# EH4a-midi-v1_4_poprawiona_na_przysz_o.net
KiCad netlist of a schematic drawn in EAGLE
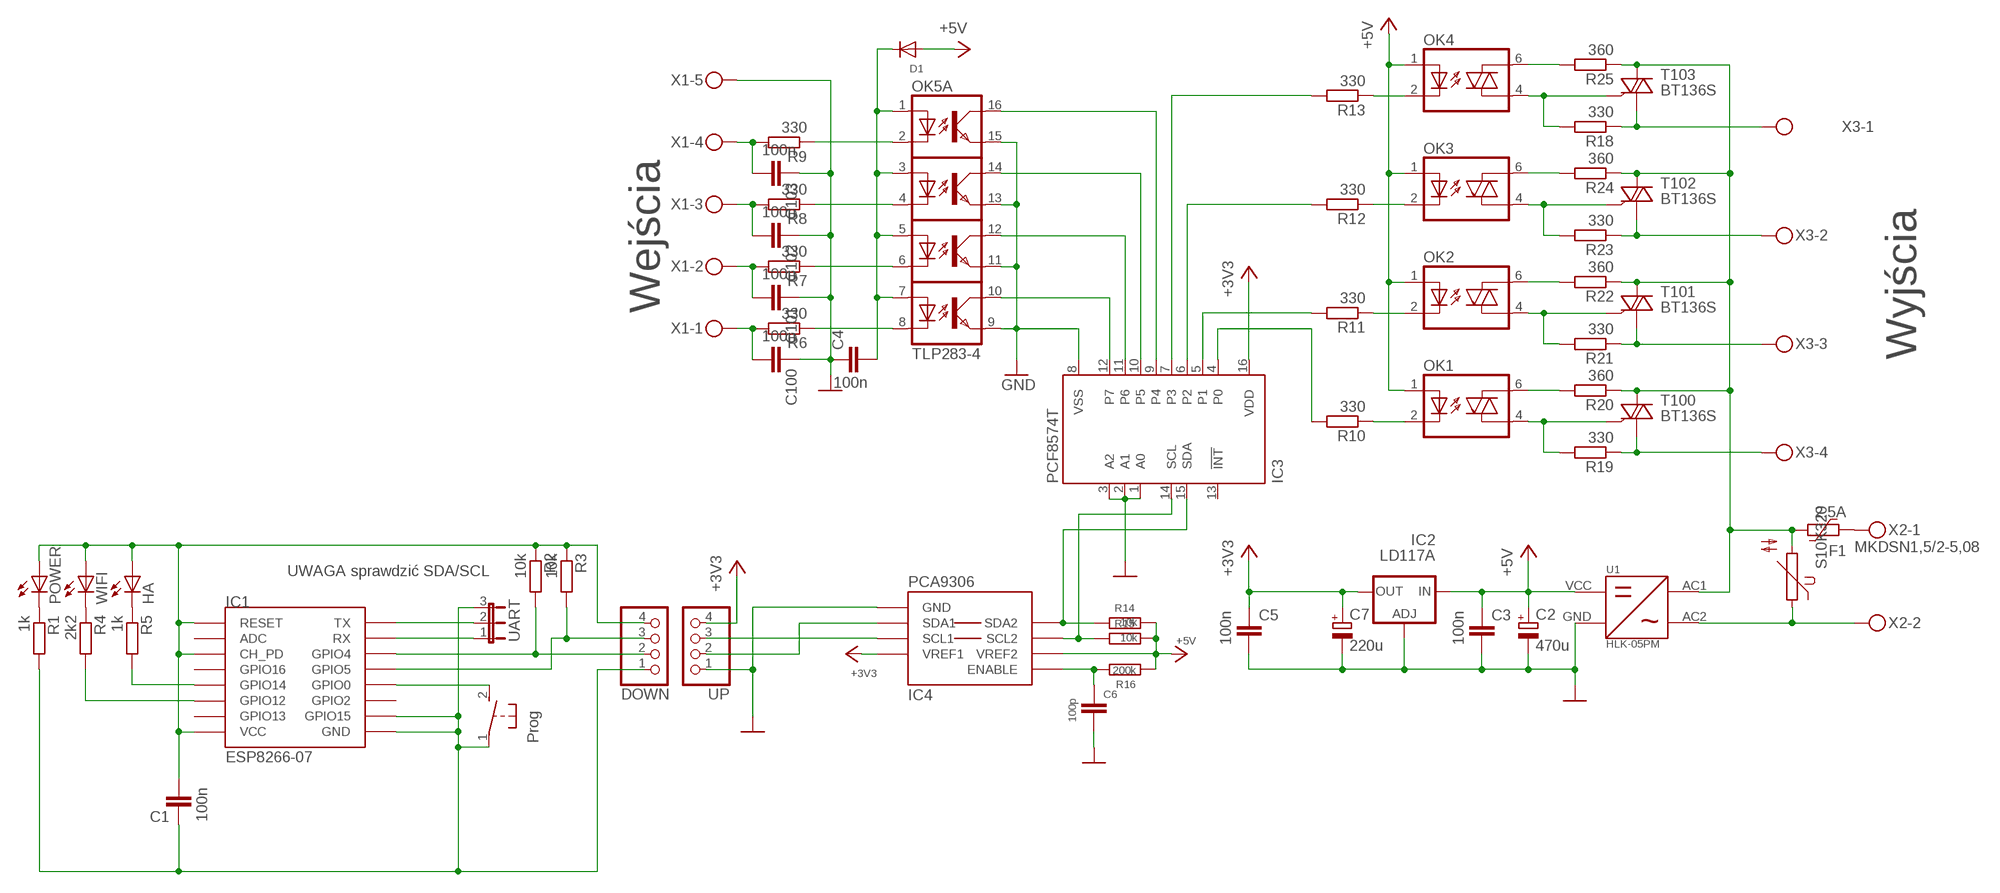
[diagram p0: schematic, sheet 1]

(export (version "E")
  (design (tool "Eeschema 10.0.6"))
  (components
    (comp (ref "C1")
      (value "100n")
      (footprint "eagle-import:C0805")
      (libsource (lib "eagle-import") (part "C-EUC0805"))
    )
    (comp (ref "C2")
      (value "470u")
      (footprint "eagle-import:E3,5-8")
      (libsource (lib "eagle-import") (part "CPOL-EUE3.5-8"))
    )
    (comp (ref "C3")
      (value "100n")
      (footprint "eagle-import:C0805")
      (libsource (lib "eagle-import") (part "C-EUC0805"))
    )
    (comp (ref "C4")
      (value "100n")
      (footprint "eagle-import:C0805")
      (libsource (lib "eagle-import") (part "C-EUC0805"))
    )
    (comp (ref "C5")
      (value "100n")
      (footprint "eagle-import:C0805")
      (libsource (lib "eagle-import") (part "C-EUC0805"))
    )
    (comp (ref "C6")
      (value "100p")
      (footprint "eagle-import:C0805")
      (libsource (lib "eagle-import") (part "C-EUC0805"))
    )
    (comp (ref "C7")
      (value "220u")
      (footprint "eagle-import:E2,5-7")
      (libsource (lib "eagle-import") (part "CPOL-EUE2.5-7"))
    )
    (comp (ref "C100")
      (value "100n")
      (footprint "eagle-import:C0805")
      (libsource (lib "eagle-import") (part "C-EUC0805"))
    )
    (comp (ref "C101")
      (value "100n")
      (footprint "eagle-import:C0805")
      (libsource (lib "eagle-import") (part "C-EUC0805"))
    )
    (comp (ref "C102")
      (value "100n")
      (footprint "eagle-import:C0805")
      (libsource (lib "eagle-import") (part "C-EUC0805"))
    )
    (comp (ref "C103")
      (value "100n")
      (footprint "eagle-import:C0805")
      (libsource (lib "eagle-import") (part "C-EUC0805"))
    )
    (comp (ref "D1")
      (value "1N4148")
      (footprint "eagle-import:SOD-123")
      (libsource (lib "eagle-import") (part "DIODESOD-123"))
    )
    (comp (ref "DOWN")
      (value "PINHD-1X4")
      (footprint "eagle-import:1X04")
      (libsource (lib "eagle-import") (part "PINHD-1X4"))
    )
    (comp (ref "F1")
      (value "2.5A")
      (footprint "eagle-import:2920L")
      (fields (field (name "MF") "Littelfuse") (field (name "MPN") "2920L700SL"))
      (libsource (lib "eagle-import") (part "?2920L700SL"))
    )
    (comp (ref "HA")
      (value "LED3MM")
      (footprint "eagle-import:LED3MM")
      (libsource (lib "eagle-import") (part "LED3MM"))
    )
    (comp (ref "IC1")
      (value "ESP8266-07")
      (footprint "eagle-import:ESP12")
      (libsource (lib "eagle-import") (part "ESP12"))
    )
    (comp (ref "IC2")
      (value "LD117A")
      (footprint "eagle-import:SOT223")
      (libsource (lib "eagle-import") (part "LD117A?S12TR"))
    )
    (comp (ref "IC3")
      (value "PCF8574T")
      (footprint "eagle-import:SO16W")
      (fields (field (name "MPN") "PCF8574T/3,512"))
      (libsource (lib "eagle-import") (part "PCF8574T"))
    )
    (comp (ref "IC4")
      (value "PCA9306")
      (footprint "eagle-import:MSOP08")
      (libsource (lib "eagle-import") (part "IC2_LEVEL_TRANSLATER"))
    )
    (comp (ref "OK1")
      (value "MOC3043")
      (footprint "eagle-import:DIL06")
      (libsource (lib "eagle-import") (part "IL420"))
    )
    (comp (ref "OK2")
      (value "IL420")
      (footprint "eagle-import:DIL06")
      (libsource (lib "eagle-import") (part "IL420"))
    )
    (comp (ref "OK3")
      (value "IL420")
      (footprint "eagle-import:DIL06")
      (libsource (lib "eagle-import") (part "IL420"))
    )
    (comp (ref "OK4")
      (value "IL420")
      (footprint "eagle-import:DIL06")
      (libsource (lib "eagle-import") (part "IL420"))
    )
    (comp (ref "OK5")
      (value "TLP283-4")
      (footprint "eagle-import:MINI-FLAT-16")
      (libsource (lib "eagle-import") (part "TLP283-4"))
    )
    (comp (ref "POWER")
      (value "LED3MM")
      (footprint "eagle-import:LED3MM")
      (libsource (lib "eagle-import") (part "LED3MM"))
    )
    (comp (ref "R1")
      (value "1k")
      (footprint "eagle-import:M0805")
      (libsource (lib "eagle-import") (part "rcl_334_R-EU_M0805"))
    )
    (comp (ref "R2")
      (value "10k")
      (footprint "eagle-import:M0805")
      (libsource (lib "eagle-import") (part "rcl_334_R-EU_M0805"))
    )
    (comp (ref "R3")
      (value "10k")
      (footprint "eagle-import:M0805")
      (libsource (lib "eagle-import") (part "rcl_334_R-EU_M0805"))
    )
    (comp (ref "R4")
      (value "2k2")
      (footprint "eagle-import:M0805")
      (libsource (lib "eagle-import") (part "rcl_334_R-EU_M0805"))
    )
    (comp (ref "R5")
      (value "1k")
      (footprint "eagle-import:M0805")
      (libsource (lib "eagle-import") (part "rcl_334_R-EU_M0805"))
    )
    (comp (ref "R6")
      (value "330")
      (footprint "eagle-import:M0805")
      (libsource (lib "eagle-import") (part "rcl_334_R-EU_M0805"))
    )
    (comp (ref "R7")
      (value "330")
      (footprint "eagle-import:M0805")
      (libsource (lib "eagle-import") (part "rcl_334_R-EU_M0805"))
    )
    (comp (ref "R8")
      (value "330")
      (footprint "eagle-import:M0805")
      (libsource (lib "eagle-import") (part "rcl_334_R-EU_M0805"))
    )
    (comp (ref "R9")
      (value "330")
      (footprint "eagle-import:M0805")
      (libsource (lib "eagle-import") (part "rcl_334_R-EU_M0805"))
    )
    (comp (ref "R10")
      (value "330")
      (footprint "eagle-import:M0805")
      (libsource (lib "eagle-import") (part "rcl_334_R-EU_M0805"))
    )
    (comp (ref "R11")
      (value "330")
      (footprint "eagle-import:M0805")
      (libsource (lib "eagle-import") (part "rcl_334_R-EU_M0805"))
    )
    (comp (ref "R12")
      (value "330")
      (footprint "eagle-import:M0805")
      (libsource (lib "eagle-import") (part "rcl_334_R-EU_M0805"))
    )
    (comp (ref "R13")
      (value "330")
      (footprint "eagle-import:M0805")
      (libsource (lib "eagle-import") (part "rcl_334_R-EU_M0805"))
    )
    (comp (ref "R14")
      (value "10k")
      (footprint "eagle-import:R0805")
      (libsource (lib "eagle-import") (part "R-EU_R0805"))
    )
    (comp (ref "R15")
      (value "10k")
      (footprint "eagle-import:R0805")
      (libsource (lib "eagle-import") (part "R-EU_R0805"))
    )
    (comp (ref "R16")
      (value "200k")
      (footprint "eagle-import:R0805")
      (libsource (lib "eagle-import") (part "R-EU_R0805"))
    )
    (comp (ref "R17")
      (value "S10K320")
      (footprint "eagle-import:S10K320")
      (libsource (lib "eagle-import") (part "S10K320"))
    )
    (comp (ref "R18")
      (value "330")
      (footprint "eagle-import:R1210")
      (libsource (lib "eagle-import") (part "R-EU_R1210"))
    )
    (comp (ref "R19")
      (value "330")
      (footprint "eagle-import:R1210")
      (libsource (lib "eagle-import") (part "R-EU_R1210"))
    )
    (comp (ref "R20")
      (value "360")
      (footprint "eagle-import:R1210")
      (libsource (lib "eagle-import") (part "R-EU_R1210"))
    )
    (comp (ref "R21")
      (value "330")
      (footprint "eagle-import:R1210")
      (libsource (lib "eagle-import") (part "R-EU_R1210"))
    )
    (comp (ref "R22")
      (value "360")
      (footprint "eagle-import:R1210")
      (libsource (lib "eagle-import") (part "R-EU_R1210"))
    )
    (comp (ref "R23")
      (value "330")
      (footprint "eagle-import:R1210")
      (libsource (lib "eagle-import") (part "R-EU_R1210"))
    )
    (comp (ref "R24")
      (value "360")
      (footprint "eagle-import:R1210")
      (libsource (lib "eagle-import") (part "R-EU_R1210"))
    )
    (comp (ref "R25")
      (value "360")
      (footprint "eagle-import:R1210")
      (libsource (lib "eagle-import") (part "R-EU_R1210"))
    )
    (comp (ref "S1")
      (value "Prog")
      (footprint "eagle-import:DTSM-3")
      (libsource (lib "eagle-import") (part "DTSM-3"))
    )
    (comp (ref "T100")
      (value "BT136S")
      (footprint "eagle-import:SOT428")
      (libsource (lib "eagle-import") (part "ACT108WDPAK"))
    )
    (comp (ref "T101")
      (value "BT136S")
      (footprint "eagle-import:SOT428")
      (libsource (lib "eagle-import") (part "ACT108WDPAK"))
    )
    (comp (ref "T102")
      (value "BT136S")
      (footprint "eagle-import:SOT428")
      (libsource (lib "eagle-import") (part "ACT108WDPAK"))
    )
    (comp (ref "T103")
      (value "BT136S")
      (footprint "eagle-import:SOT428")
      (libsource (lib "eagle-import") (part "ACT108WDPAK"))
    )
    (comp (ref "U1")
      (value "HLK-05PM")
      (footprint "eagle-import:HLK-PM01_HLK-PM01")
      (libsource (lib "eagle-import") (part "HLK-PM01_HLK-PM01"))
    )
    (comp (ref "UART")
      (value "JP2E")
      (footprint "eagle-import:JP2")
      (libsource (lib "eagle-import") (part "JP2E"))
    )
    (comp (ref "UP")
      (value "PINHD-1X4")
      (footprint "eagle-import:1X04")
      (libsource (lib "eagle-import") (part "PINHD-1X4"))
    )
    (comp (ref "WIFI")
      (value "LED3MM")
      (footprint "eagle-import:LED3MM")
      (libsource (lib "eagle-import") (part "LED3MM"))
    )
    (comp (ref "X1")
      (value "MKDSN1,5/5-5,08")
      (footprint "eagle-import:MKDSN1,5_5-5,08")
      (libsource (lib "eagle-import") (part "MKDSN1,5/5-5,08"))
    )
    (comp (ref "X2")
      (value "MKDSN1,5/2-5,08")
      (footprint "eagle-import:MKDSN1,5_2-5,08")
      (libsource (lib "eagle-import") (part "MKDSN1,5/2-5,08"))
    )
    (comp (ref "X3")
      (value "MKDSN1,5/4-5,08")
      (footprint "eagle-import:MKDSN1,5_4-5,08")
      (libsource (lib "eagle-import") (part "MKDSN1,5/4-5,08"))
    )
  )
  (nets
    (net (code "1") (name "+3V3") (class "Default")
      (node (ref "C5") (pin "1") (pinfunction "1_1") (pintype "passive"))
      (node (ref "C7") (pin "+") (pinfunction "+_+") (pintype "passive"))
      (node (ref "IC2") (pin "2") (pinfunction "OUT_2") (pintype "passive"))
      (node (ref "IC2") (pin "4") (pinfunction "OUT_4") (pintype "passive"))
      (node (ref "IC3") (pin "16") (pinfunction "VDD_16") (pintype "power_in"))
      (node (ref "IC4") (pin "2") (pinfunction "VREF1_2") (pintype "power_in"))
      (node (ref "UP") (pin "4") (pinfunction "4_4") (pintype "passive"))
    )
    (net (code "2") (name "+5V") (class "Default")
      (node (ref "C2") (pin "+") (pinfunction "+_+") (pintype "passive"))
      (node (ref "C3") (pin "1") (pinfunction "1_1") (pintype "passive"))
      (node (ref "D1") (pin "A") (pinfunction "A_A") (pintype "passive"))
      (node (ref "IC2") (pin "3") (pinfunction "IN_3") (pintype "input"))
      (node (ref "IC4") (pin "7") (pinfunction "VREF2_7") (pintype "power_in"))
      (node (ref "OK1") (pin "1") (pinfunction "A_1") (pintype "passive"))
      (node (ref "OK2") (pin "1") (pinfunction "A_1") (pintype "passive"))
      (node (ref "OK3") (pin "1") (pinfunction "A_1") (pintype "passive"))
      (node (ref "OK4") (pin "1") (pinfunction "A_1") (pintype "passive"))
      (node (ref "R14") (pin "1") (pinfunction "1_1") (pintype "passive"))
      (node (ref "R15") (pin "1") (pinfunction "1_1") (pintype "passive"))
      (node (ref "R16") (pin "2") (pinfunction "2_2") (pintype "passive"))
      (node (ref "U1") (pin "VCC") (pinfunction "VCC_VCC") (pintype "power_in"))
    )
    (net (code "3") (name "GND") (class "Default")
      (node (ref "C100") (pin "1") (pinfunction "1_1") (pintype "passive"))
      (node (ref "C101") (pin "1") (pinfunction "1_1") (pintype "passive"))
      (node (ref "C102") (pin "1") (pinfunction "1_1") (pintype "passive"))
      (node (ref "C103") (pin "1") (pinfunction "1_1") (pintype "passive"))
      (node (ref "C2") (pin "-") (pinfunction "-_-") (pintype "passive"))
      (node (ref "C3") (pin "2") (pinfunction "2_2") (pintype "passive"))
      (node (ref "C4") (pin "1") (pinfunction "1_1") (pintype "passive"))
      (node (ref "C5") (pin "2") (pinfunction "2_2") (pintype "passive"))
      (node (ref "C6") (pin "2") (pinfunction "2_2") (pintype "passive"))
      (node (ref "C7") (pin "-") (pinfunction "-_-") (pintype "passive"))
      (node (ref "IC2") (pin "1") (pinfunction "ADJ_1") (pintype "input"))
      (node (ref "IC3") (pin "1") (pinfunction "A0_1") (pintype "input"))
      (node (ref "IC3") (pin "2") (pinfunction "A1_2") (pintype "input"))
      (node (ref "IC3") (pin "3") (pinfunction "A2_3") (pintype "input"))
      (node (ref "IC3") (pin "8") (pinfunction "VSS_8") (pintype "power_in"))
      (node (ref "IC4") (pin "1") (pinfunction "GND_1") (pintype "power_in"))
      (node (ref "OK5") (pin "11") (pinfunction "EMIT_11") (pintype "passive"))
      (node (ref "OK5") (pin "13") (pinfunction "EMIT_13") (pintype "passive"))
      (node (ref "OK5") (pin "15") (pinfunction "EMIT_15") (pintype "passive"))
      (node (ref "OK5") (pin "9") (pinfunction "EMIT_9") (pintype "passive"))
      (node (ref "U1") (pin "GND") (pinfunction "GND_GND") (pintype "power_in"))
      (node (ref "UP") (pin "1") (pinfunction "1_1") (pintype "passive"))
      (node (ref "X1") (pin "5") (pinfunction "KL_5") (pintype "passive"))
    )
    (net (code "4") (name "Net-(C1-Pad1)") (class "Default")
      (node (ref "C1") (pin "1") (pinfunction "1_1") (pintype "passive"))
      (node (ref "DOWN") (pin "1") (pinfunction "1_1") (pintype "passive"))
      (node (ref "IC1") (pin "GND") (pinfunction "GND_GND") (pintype "bidirectional"))
      (node (ref "IC1") (pin "GPIO15") (pinfunction "GPIO15_GPIO15") (pintype "bidirectional"))
      (node (ref "R1") (pin "2") (pinfunction "2_2") (pintype "passive"))
      (node (ref "S1") (pin "1") (pinfunction "1_1") (pintype "passive"))
      (node (ref "UART") (pin "3") (pinfunction "3_3") (pintype "passive"))
    )
    (net (code "5") (name "Net-(C1-Pad2)") (class "Default")
      (node (ref "C1") (pin "2") (pinfunction "2_2") (pintype "passive"))
      (node (ref "DOWN") (pin "4") (pinfunction "4_4") (pintype "passive"))
      (node (ref "HA") (pin "A") (pinfunction "A_A") (pintype "passive"))
      (node (ref "IC1") (pin "CH_PD") (pinfunction "CH_PD_CH_PD") (pintype "bidirectional"))
      (node (ref "IC1") (pin "RESET") (pinfunction "RESET_RESET") (pintype "bidirectional"))
      (node (ref "IC1") (pin "VCC") (pinfunction "VCC_VCC") (pintype "bidirectional"))
      (node (ref "POWER") (pin "A") (pinfunction "A_A") (pintype "passive"))
      (node (ref "R2") (pin "1") (pinfunction "1_1") (pintype "passive"))
      (node (ref "R3") (pin "1") (pinfunction "1_1") (pintype "passive"))
      (node (ref "WIFI") (pin "A") (pinfunction "A_A") (pintype "passive"))
    )
    (net (code "6") (name "Net-(DOWN-Pad2)") (class "Default")
      (node (ref "DOWN") (pin "2") (pinfunction "2_2") (pintype "passive"))
      (node (ref "IC1") (pin "GPIO4") (pinfunction "GPIO4_GPIO4") (pintype "bidirectional"))
      (node (ref "R2") (pin "2") (pinfunction "2_2") (pintype "passive"))
    )
    (net (code "7") (name "Net-(DOWN-Pad3)") (class "Default")
      (node (ref "DOWN") (pin "3") (pinfunction "3_3") (pintype "passive"))
      (node (ref "IC1") (pin "GPIO5") (pinfunction "GPIO5_GPIO5") (pintype "bidirectional"))
      (node (ref "R3") (pin "2") (pinfunction "2_2") (pintype "passive"))
    )
    (net (code "8") (name "Net-(HA-C)") (class "Default")
      (node (ref "HA") (pin "K") (pinfunction "C_K") (pintype "passive"))
      (node (ref "R5") (pin "1") (pinfunction "1_1") (pintype "passive"))
    )
    (net (code "9") (name "Net-(IC1-PadGPIO0)") (class "Default")
      (node (ref "IC1") (pin "GPIO0") (pinfunction "GPIO0_GPIO0") (pintype "bidirectional"))
      (node (ref "S1") (pin "2") (pinfunction "2_2") (pintype "passive"))
    )
    (net (code "10") (name "Net-(IC1-PadGPIO12)") (class "Default")
      (node (ref "IC1") (pin "GPIO12") (pinfunction "GPIO12_GPIO12") (pintype "bidirectional"))
      (node (ref "R4") (pin "2") (pinfunction "2_2") (pintype "passive"))
    )
    (net (code "11") (name "Net-(IC1-PadGPIO14)") (class "Default")
      (node (ref "IC1") (pin "GPIO14") (pinfunction "GPIO14_GPIO14") (pintype "bidirectional"))
      (node (ref "R5") (pin "2") (pinfunction "2_2") (pintype "passive"))
    )
    (net (code "12") (name "Net-(IC1-PadRX)") (class "Default")
      (node (ref "IC1") (pin "RX") (pinfunction "RX_RX") (pintype "bidirectional"))
      (node (ref "UART") (pin "1") (pinfunction "1_1") (pintype "passive"))
    )
    (net (code "13") (name "Net-(IC1-PadTX)") (class "Default")
      (node (ref "IC1") (pin "TX") (pinfunction "TX_TX") (pintype "bidirectional"))
      (node (ref "UART") (pin "2") (pinfunction "2_2") (pintype "passive"))
    )
    (net (code "14") (name "Net-(IC3-P0)") (class "Default")
      (node (ref "IC3") (pin "4") (pinfunction "P0_4") (pintype "bidirectional"))
      (node (ref "R10") (pin "2") (pinfunction "2_2") (pintype "passive"))
    )
    (net (code "15") (name "Net-(IC3-P1)") (class "Default")
      (node (ref "IC3") (pin "5") (pinfunction "P1_5") (pintype "bidirectional"))
      (node (ref "R11") (pin "2") (pinfunction "2_2") (pintype "passive"))
    )
    (net (code "16") (name "Net-(IC3-P2)") (class "Default")
      (node (ref "IC3") (pin "6") (pinfunction "P2_6") (pintype "bidirectional"))
      (node (ref "R12") (pin "2") (pinfunction "2_2") (pintype "passive"))
    )
    (net (code "17") (name "Net-(IC3-P3)") (class "Default")
      (node (ref "IC3") (pin "7") (pinfunction "P3_7") (pintype "bidirectional"))
      (node (ref "R13") (pin "2") (pinfunction "2_2") (pintype "passive"))
    )
    (net (code "18") (name "Net-(IC3-P4)") (class "Default")
      (node (ref "IC3") (pin "9") (pinfunction "P4_9") (pintype "bidirectional"))
      (node (ref "OK5") (pin "16") (pinfunction "COL_16") (pintype "passive"))
    )
    (net (code "19") (name "Net-(IC3-P5)") (class "Default")
      (node (ref "IC3") (pin "10") (pinfunction "P5_10") (pintype "bidirectional"))
      (node (ref "OK5") (pin "14") (pinfunction "COL_14") (pintype "passive"))
    )
    (net (code "20") (name "Net-(IC3-P6)") (class "Default")
      (node (ref "IC3") (pin "11") (pinfunction "P6_11") (pintype "bidirectional"))
      (node (ref "OK5") (pin "12") (pinfunction "COL_12") (pintype "passive"))
    )
    (net (code "21") (name "Net-(IC3-P7)") (class "Default")
      (node (ref "IC3") (pin "12") (pinfunction "P7_12") (pintype "bidirectional"))
      (node (ref "OK5") (pin "10") (pinfunction "COL_10") (pintype "passive"))
    )
    (net (code "22") (name "Net-(IC3-SCL)") (class "Default")
      (node (ref "IC3") (pin "14") (pinfunction "SCL_14") (pintype "input"))
      (node (ref "IC4") (pin "6") (pinfunction "SCL2_6") (pintype "bidirectional"))
      (node (ref "R15") (pin "2") (pinfunction "2_2") (pintype "passive"))
    )
    (net (code "23") (name "Net-(IC3-SDA)") (class "Default")
      (node (ref "IC3") (pin "15") (pinfunction "SDA_15") (pintype "bidirectional"))
      (node (ref "IC4") (pin "5") (pinfunction "SDA2_5") (pintype "bidirectional"))
      (node (ref "R14") (pin "2") (pinfunction "2_2") (pintype "passive"))
    )
    (net (code "24") (name "Net-(IC4-ENABLE)") (class "Default")
      (node (ref "C6") (pin "1") (pinfunction "1_1") (pintype "passive"))
      (node (ref "IC4") (pin "8") (pinfunction "ENABLE_8") (pintype "input"))
      (node (ref "R16") (pin "1") (pinfunction "1_1") (pintype "passive"))
    )
    (net (code "25") (name "Net-(IC4-SCL1)") (class "Default")
      (node (ref "IC4") (pin "3") (pinfunction "SCL1_3") (pintype "bidirectional"))
      (node (ref "UP") (pin "3") (pinfunction "3_3") (pintype "passive"))
    )
    (net (code "26") (name "Net-(IC4-SDA1)") (class "Default")
      (node (ref "IC4") (pin "4") (pinfunction "SDA1_4") (pintype "bidirectional"))
      (node (ref "UP") (pin "2") (pinfunction "2_2") (pintype "passive"))
    )
    (net (code "27") (name "Net-(OK1-A1)") (class "Default")
      (node (ref "OK1") (pin "4") (pinfunction "A1_4") (pintype "passive"))
      (node (ref "R19") (pin "2") (pinfunction "2_2") (pintype "passive"))
      (node (ref "T100") (pin "3") (pinfunction "G_3") (pintype "passive"))
    )
    (net (code "28") (name "Net-(OK1-A2)") (class "Default")
      (node (ref "OK1") (pin "6") (pinfunction "A2_6") (pintype "passive"))
      (node (ref "R20") (pin "2") (pinfunction "2_2") (pintype "passive"))
    )
    (net (code "29") (name "Net-(OK1-C)") (class "Default")
      (node (ref "OK1") (pin "2") (pinfunction "C_2") (pintype "passive"))
      (node (ref "R10") (pin "1") (pinfunction "1_1") (pintype "passive"))
    )
    (net (code "30") (name "Net-(OK2-A1)") (class "Default")
      (node (ref "OK2") (pin "4") (pinfunction "A1_4") (pintype "passive"))
      (node (ref "R21") (pin "2") (pinfunction "2_2") (pintype "passive"))
      (node (ref "T101") (pin "3") (pinfunction "G_3") (pintype "passive"))
    )
    (net (code "31") (name "Net-(OK2-A2)") (class "Default")
      (node (ref "OK2") (pin "6") (pinfunction "A2_6") (pintype "passive"))
      (node (ref "R22") (pin "2") (pinfunction "2_2") (pintype "passive"))
    )
    (net (code "32") (name "Net-(OK2-C)") (class "Default")
      (node (ref "OK2") (pin "2") (pinfunction "C_2") (pintype "passive"))
      (node (ref "R11") (pin "1") (pinfunction "1_1") (pintype "passive"))
    )
    (net (code "33") (name "Net-(OK3-A1)") (class "Default")
      (node (ref "OK3") (pin "4") (pinfunction "A1_4") (pintype "passive"))
      (node (ref "R23") (pin "2") (pinfunction "2_2") (pintype "passive"))
      (node (ref "T102") (pin "3") (pinfunction "G_3") (pintype "passive"))
    )
    (net (code "34") (name "Net-(OK3-A2)") (class "Default")
      (node (ref "OK3") (pin "6") (pinfunction "A2_6") (pintype "passive"))
      (node (ref "R24") (pin "2") (pinfunction "2_2") (pintype "passive"))
    )
    (net (code "35") (name "Net-(OK3-C)") (class "Default")
      (node (ref "OK3") (pin "2") (pinfunction "C_2") (pintype "passive"))
      (node (ref "R12") (pin "1") (pinfunction "1_1") (pintype "passive"))
    )
    (net (code "36") (name "Net-(OK4-A1)") (class "Default")
      (node (ref "OK4") (pin "4") (pinfunction "A1_4") (pintype "passive"))
      (node (ref "R18") (pin "2") (pinfunction "2_2") (pintype "passive"))
      (node (ref "T103") (pin "3") (pinfunction "G_3") (pintype "passive"))
    )
    (net (code "37") (name "Net-(OK4-A2)") (class "Default")
      (node (ref "OK4") (pin "6") (pinfunction "A2_6") (pintype "passive"))
      (node (ref "R25") (pin "2") (pinfunction "2_2") (pintype "passive"))
    )
    (net (code "38") (name "Net-(OK4-C)") (class "Default")
      (node (ref "OK4") (pin "2") (pinfunction "C_2") (pintype "passive"))
      (node (ref "R13") (pin "1") (pinfunction "1_1") (pintype "passive"))
    )
    (net (code "39") (name "Net-(OK5A-A)") (class "Default")
      (node (ref "C4") (pin "2") (pinfunction "2_2") (pintype "passive"))
      (node (ref "D1") (pin "C") (pinfunction "C_C") (pintype "passive"))
      (node (ref "OK5") (pin "1") (pinfunction "A_1") (pintype "passive"))
      (node (ref "OK5") (pin "3") (pinfunction "A_3") (pintype "passive"))
      (node (ref "OK5") (pin "5") (pinfunction "A_5") (pintype "passive"))
      (node (ref "OK5") (pin "7") (pinfunction "A_7") (pintype "passive"))
    )
    (net (code "40") (name "Net-(OK5A-C)") (class "Default")
      (node (ref "OK5") (pin "2") (pinfunction "C_2") (pintype "passive"))
      (node (ref "R9") (pin "1") (pinfunction "1_1") (pintype "passive"))
    )
    (net (code "41") (name "Net-(OK5B-C)") (class "Default")
      (node (ref "OK5") (pin "4") (pinfunction "C_4") (pintype "passive"))
      (node (ref "R8") (pin "1") (pinfunction "1_1") (pintype "passive"))
    )
    (net (code "42") (name "Net-(OK5C-C)") (class "Default")
      (node (ref "OK5") (pin "6") (pinfunction "C_6") (pintype "passive"))
      (node (ref "R7") (pin "1") (pinfunction "1_1") (pintype "passive"))
    )
    (net (code "43") (name "Net-(OK5D-C)") (class "Default")
      (node (ref "OK5") (pin "8") (pinfunction "C_8") (pintype "passive"))
      (node (ref "R6") (pin "1") (pinfunction "1_1") (pintype "passive"))
    )
    (net (code "44") (name "Net-(POWER-C)") (class "Default")
      (node (ref "POWER") (pin "K") (pinfunction "C_K") (pintype "passive"))
      (node (ref "R1") (pin "1") (pinfunction "1_1") (pintype "passive"))
    )
    (net (code "45") (name "Net-(T100-CM)") (class "Default")
      (node (ref "R19") (pin "1") (pinfunction "1_1") (pintype "passive"))
      (node (ref "T100") (pin "1") (pinfunction "CM_1") (pintype "passive"))
      (node (ref "X3") (pin "4") (pinfunction "KL_4") (pintype "passive"))
    )
    (net (code "46") (name "Net-(T100-LD)") (class "Default")
      (node (ref "F1") (pin "1") (pinfunction "1_1") (pintype "passive"))
      (node (ref "R17") (pin "2") (pinfunction "2_2") (pintype "passive"))
      (node (ref "R20") (pin "1") (pinfunction "1_1") (pintype "passive"))
      (node (ref "R22") (pin "1") (pinfunction "1_1") (pintype "passive"))
      (node (ref "R24") (pin "1") (pinfunction "1_1") (pintype "passive"))
      (node (ref "R25") (pin "1") (pinfunction "1_1") (pintype "passive"))
      (node (ref "T100") (pin "MB") (pinfunction "LD_MB") (pintype "passive"))
      (node (ref "T101") (pin "MB") (pinfunction "LD_MB") (pintype "passive"))
      (node (ref "T102") (pin "MB") (pinfunction "LD_MB") (pintype "passive"))
      (node (ref "T103") (pin "MB") (pinfunction "LD_MB") (pintype "passive"))
      (node (ref "U1") (pin "AC1") (pinfunction "AC1_AC1") (pintype "bidirectional"))
    )
    (net (code "47") (name "Net-(T101-CM)") (class "Default")
      (node (ref "R21") (pin "1") (pinfunction "1_1") (pintype "passive"))
      (node (ref "T101") (pin "1") (pinfunction "CM_1") (pintype "passive"))
      (node (ref "X3") (pin "3") (pinfunction "KL_3") (pintype "passive"))
    )
    (net (code "48") (name "Net-(T102-CM)") (class "Default")
      (node (ref "R23") (pin "1") (pinfunction "1_1") (pintype "passive"))
      (node (ref "T102") (pin "1") (pinfunction "CM_1") (pintype "passive"))
      (node (ref "X3") (pin "2") (pinfunction "KL_2") (pintype "passive"))
    )
    (net (code "49") (name "Net-(T103-CM)") (class "Default")
      (node (ref "R18") (pin "1") (pinfunction "1_1") (pintype "passive"))
      (node (ref "T103") (pin "1") (pinfunction "CM_1") (pintype "passive"))
      (node (ref "X3") (pin "1") (pinfunction "KL_1") (pintype "passive"))
    )
    (net (code "50") (name "Net-(WIFI-C)") (class "Default")
      (node (ref "R4") (pin "1") (pinfunction "1_1") (pintype "passive"))
      (node (ref "WIFI") (pin "K") (pinfunction "C_K") (pintype "passive"))
    )
    (net (code "51") (name "Net-(X1A-KL)") (class "Default")
      (node (ref "C100") (pin "2") (pinfunction "2_2") (pintype "passive"))
      (node (ref "R6") (pin "2") (pinfunction "2_2") (pintype "passive"))
      (node (ref "X1") (pin "1") (pinfunction "KL_1") (pintype "passive"))
    )
    (net (code "52") (name "Net-(X1B-KL)") (class "Default")
      (node (ref "C101") (pin "2") (pinfunction "2_2") (pintype "passive"))
      (node (ref "R7") (pin "2") (pinfunction "2_2") (pintype "passive"))
      (node (ref "X1") (pin "2") (pinfunction "KL_2") (pintype "passive"))
    )
    (net (code "53") (name "Net-(X1C-KL)") (class "Default")
      (node (ref "C102") (pin "2") (pinfunction "2_2") (pintype "passive"))
      (node (ref "R8") (pin "2") (pinfunction "2_2") (pintype "passive"))
      (node (ref "X1") (pin "3") (pinfunction "KL_3") (pintype "passive"))
    )
    (net (code "54") (name "Net-(X1D-KL)") (class "Default")
      (node (ref "C103") (pin "2") (pinfunction "2_2") (pintype "passive"))
      (node (ref "R9") (pin "2") (pinfunction "2_2") (pintype "passive"))
      (node (ref "X1") (pin "4") (pinfunction "KL_4") (pintype "passive"))
    )
    (net (code "55") (name "Net-(X2A-KL)") (class "Default")
      (node (ref "F1") (pin "2") (pinfunction "2_2") (pintype "passive"))
      (node (ref "X2") (pin "1") (pinfunction "KL_1") (pintype "passive"))
    )
    (net (code "56") (name "Net-(X2B-KL)") (class "Default")
      (node (ref "R17") (pin "1") (pinfunction "1_1") (pintype "passive"))
      (node (ref "U1") (pin "AC2") (pinfunction "AC2_AC2") (pintype "bidirectional"))
      (node (ref "X2") (pin "2") (pinfunction "KL_2") (pintype "passive"))
    )
    (net (code "57") (name "unconnected-(IC1-PadADC)") (class "Default")
      (node (ref "IC1") (pin "ADC") (pinfunction "ADC_ADC") (pintype "bidirectional"))
    )
    (net (code "58") (name "unconnected-(IC1-PadGPIO2)") (class "Default")
      (node (ref "IC1") (pin "GPIO2") (pinfunction "GPIO2_GPIO2") (pintype "bidirectional"))
    )
    (net (code "59") (name "unconnected-(IC1-PadGPIO13)") (class "Default")
      (node (ref "IC1") (pin "GPIO13") (pinfunction "GPIO13_GPIO13") (pintype "bidirectional"))
    )
    (net (code "60") (name "unconnected-(IC1-PadGPIO16)") (class "Default")
      (node (ref "IC1") (pin "GPIO16") (pinfunction "GPIO16_GPIO16") (pintype "bidirectional"))
    )
    (net (code "61") (name "unconnected-(IC3-~{INT}-Pad13)") (class "Default")
      (node (ref "IC3") (pin "13") (pinfunction "~{INT}_13") (pintype "output"))
    )
  )
)
